# MCU.net
KiCad netlist of a schematic drawn in Altium Designer
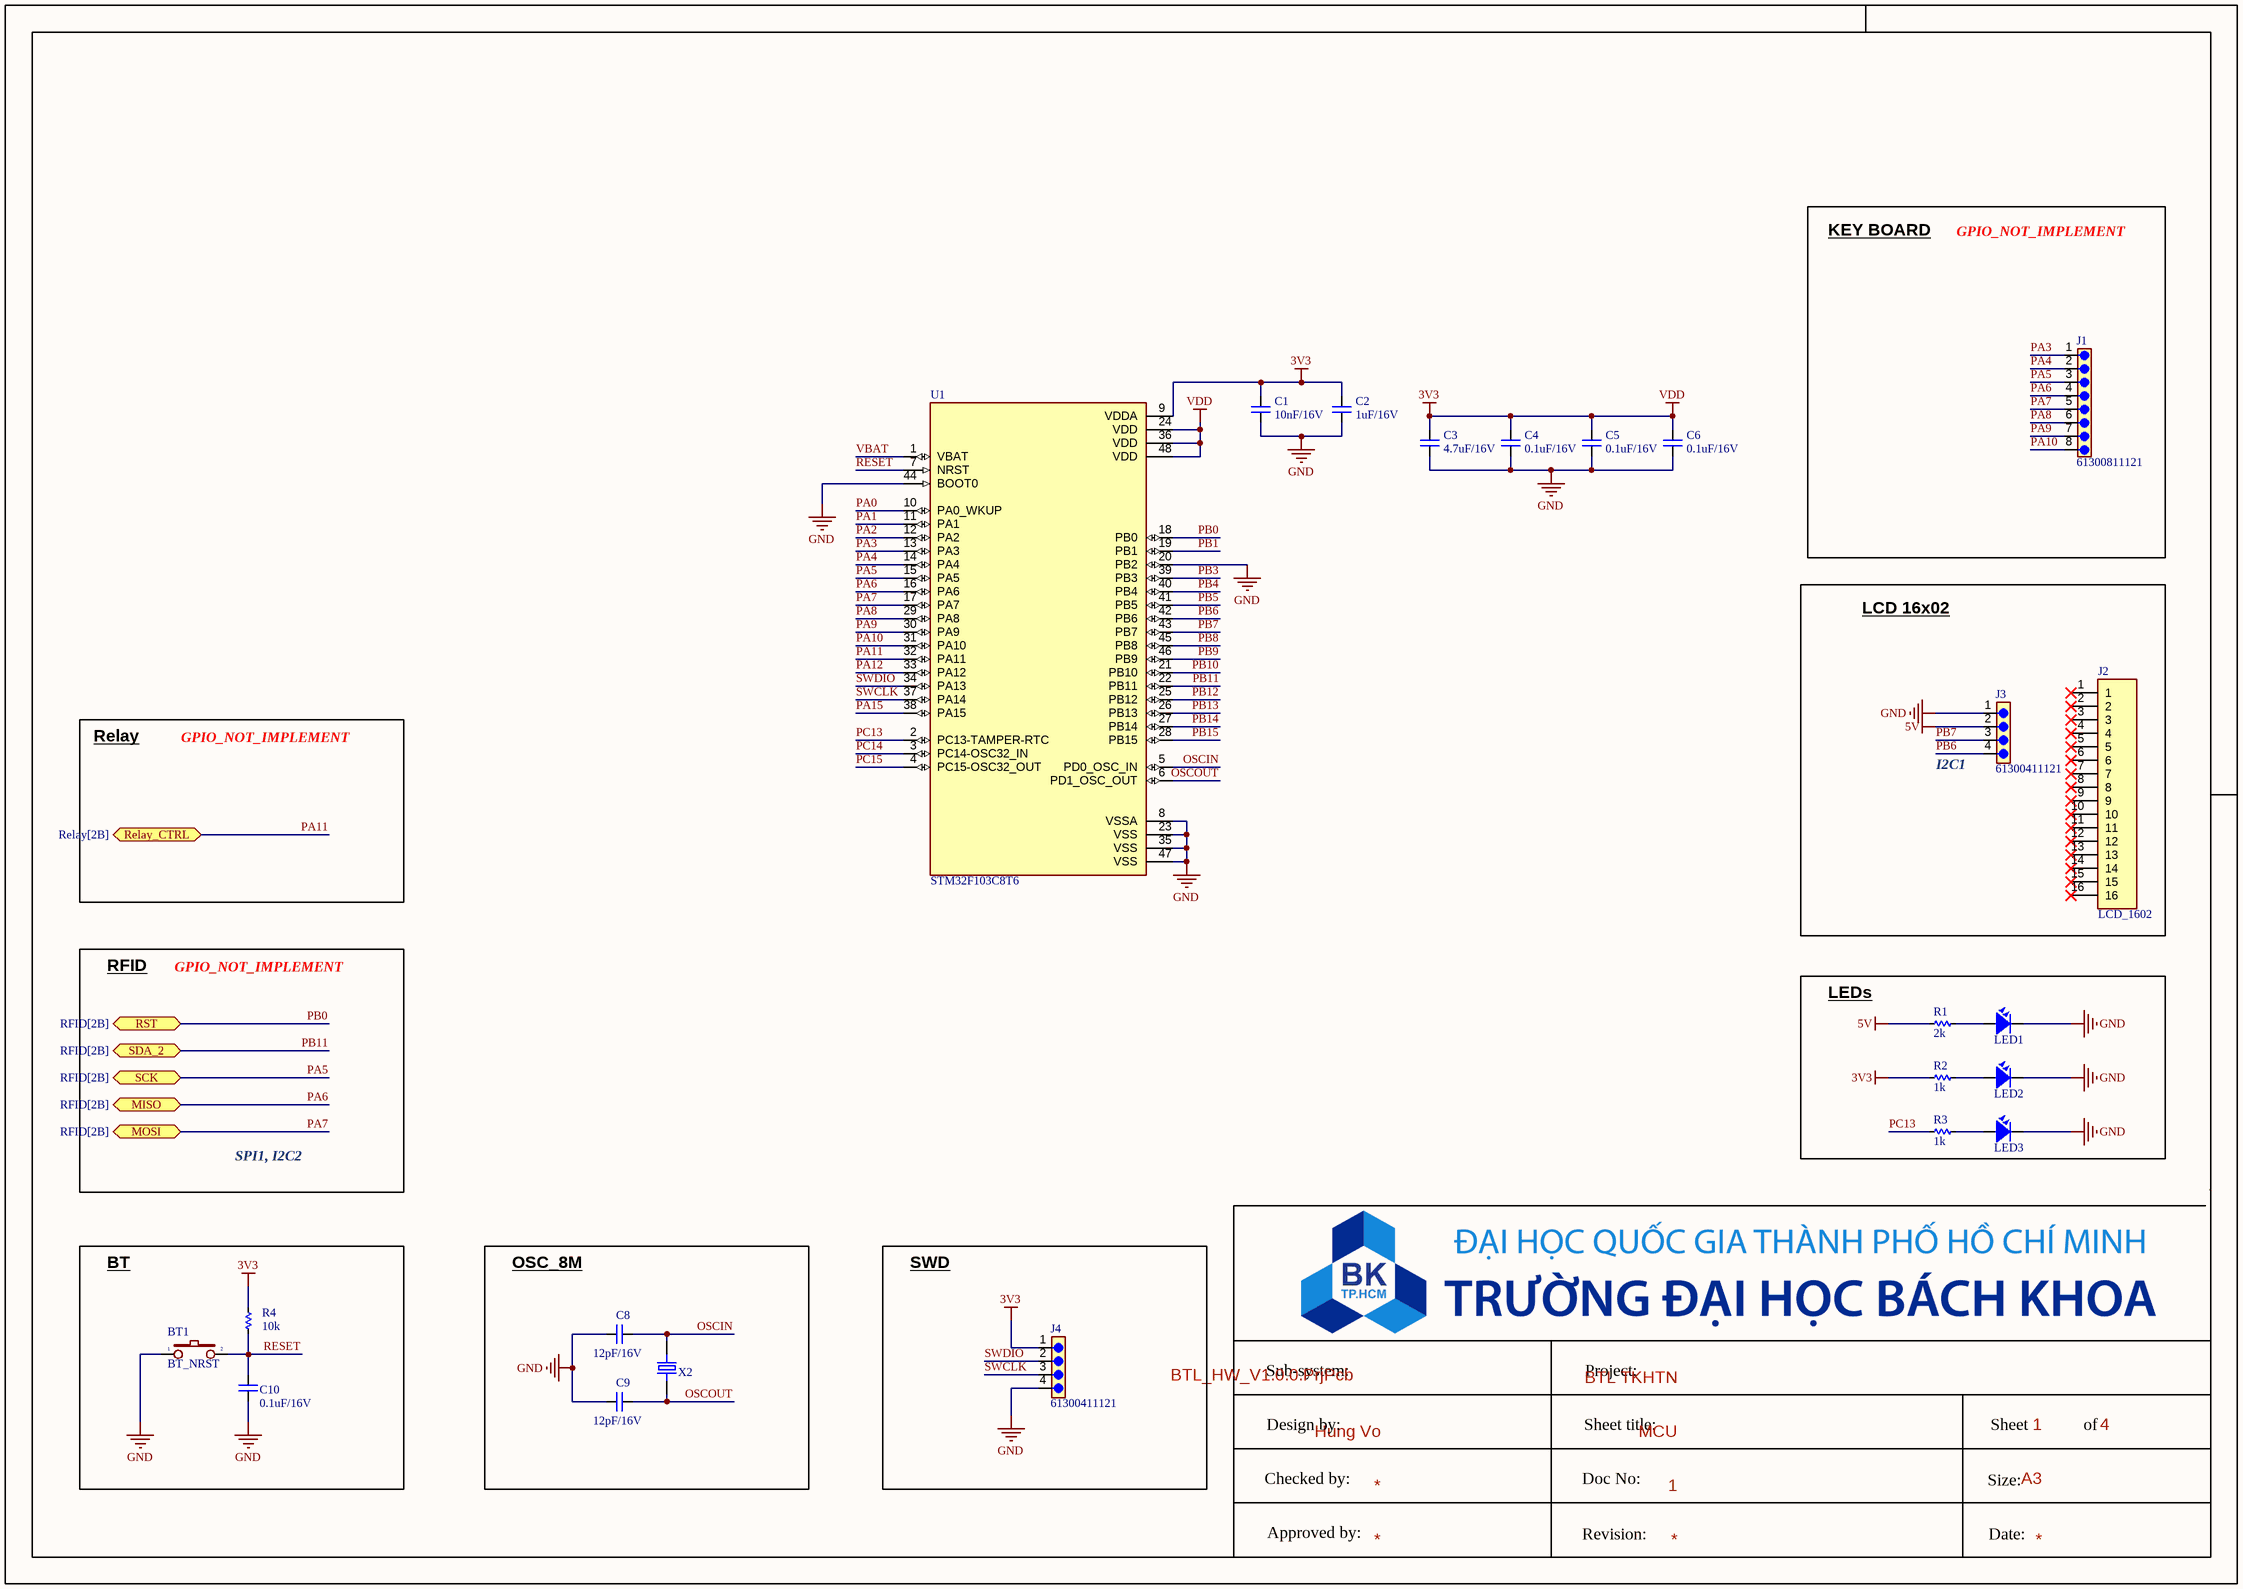
[diagram p0: MCU.SchDoc]

(export (version "E")
  (design (tool "Eeschema 10.0.6"))
  (components
    (comp (ref "BT1")
      (value "BT_NRST")
      (footprint "SW2-SMD")
      (description "Switch button 2 pin")
      (libsource (lib "C26_SCHLIB") (part "BT2"))
    )
    (comp (ref "C1")
      (value "10nF/16V")
      (footprint "CAP_C_1608X80")
      (description "CAP_Chip")
      (libsource (lib "C26_SCHLIB") (part "CAP_SMD"))
    )
    (comp (ref "C2")
      (value "1uF/16V")
      (footprint "CAP_C_1608X80")
      (description "CAP_Chip")
      (libsource (lib "C26_SCHLIB") (part "CAP_SMD"))
    )
    (comp (ref "C3")
      (value "4.7uF/16V")
      (footprint "CAP_C_1608X80")
      (description "CAP_Chip")
      (libsource (lib "C26_SCHLIB") (part "CAP_SMD"))
    )
    (comp (ref "C4")
      (value "0.1uF/16V")
      (footprint "CAP_C_1608X80")
      (description "CAP_Chip")
      (libsource (lib "C26_SCHLIB") (part "CAP_SMD"))
    )
    (comp (ref "C5")
      (value "0.1uF/16V")
      (footprint "CAP_C_1608X80")
      (description "CAP_Chip")
      (libsource (lib "C26_SCHLIB") (part "CAP_SMD"))
    )
    (comp (ref "C6")
      (value "0.1uF/16V")
      (footprint "CAP_C_1608X80")
      (description "CAP_Chip")
      (libsource (lib "C26_SCHLIB") (part "CAP_SMD"))
    )
    (comp (ref "C8")
      (value "12pF/16V")
      (footprint "CAP_C_1608X80")
      (description "CAP_Chip")
      (libsource (lib "C26_SCHLIB") (part "CAP_SMD"))
    )
    (comp (ref "C9")
      (value "12pF/16V")
      (footprint "CAP_C_1608X80")
      (description "CAP_Chip")
      (libsource (lib "C26_SCHLIB") (part "CAP_SMD"))
    )
    (comp (ref "C10")
      (value "0.1uF/16V")
      (footprint "CAP_C_1608X80")
      (description "CAP_Chip")
      (libsource (lib "C26_SCHLIB") (part "CAP_SMD"))
    )
    (comp (ref "J1")
      (value "61300811121")
      (footprint "61300811121")
      (description "8 pins, 1 row, straight, gold plating")
      (fields (field (name "MF") "Wurth Electronics"))
      (libsource (lib "BTL_SCHLIB") (part "61300811121"))
    )
    (comp (ref "J2")
      (value "LCD_1602")
      (footprint "LCD_1602")
      (libsource (lib "BTL_SCHLIB") (part "LCD_1602"))
    )
    (comp (ref "J3")
      (value "61300411121")
      (footprint "61300411121")
      (description "CONN HEADER VERT 4POS 2.54MM")
      (fields (field (name "MF") "WÃ¼rth Elektronik"))
      (libsource (lib "BTL_SCHLIB") (part "61300411121"))
    )
    (comp (ref "J4")
      (value "61300411121")
      (footprint "61300411121")
      (description "CONN HEADER VERT 4POS 2.54MM")
      (fields (field (name "MF") "WÃ¼rth Elektronik"))
      (libsource (lib "C26_SCHLIB") (part "61300411121"))
    )
    (comp (ref "LED1")
      (value "LED")
      (footprint "LED-0603-RED")
      (libsource (lib "C26_SCHLIB") (part "LED SMD"))
    )
    (comp (ref "LED2")
      (value "LED")
      (footprint "LED-0603-RED")
      (libsource (lib "C26_SCHLIB") (part "LED SMD"))
    )
    (comp (ref "LED3")
      (value "LED")
      (footprint "LED-0603-RED")
      (libsource (lib "C26_SCHLIB") (part "LED SMD"))
    )
    (comp (ref "R1")
      (value "2k")
      (footprint "RES_C_1608X60")
      (description "RES")
      (libsource (lib "C26_SCHLIB") (part "RES_SMD"))
    )
    (comp (ref "R2")
      (value "1k")
      (footprint "RES_C_1608X60")
      (description "RES")
      (libsource (lib "C26_SCHLIB") (part "RES_SMD"))
    )
    (comp (ref "R3")
      (value "1k")
      (footprint "RES_C_1608X60")
      (description "RES")
      (libsource (lib "C26_SCHLIB") (part "RES_SMD"))
    )
    (comp (ref "R4")
      (value "10k")
      (footprint "RES_C_1608X60")
      (description "RES")
      (libsource (lib "C26_SCHLIB") (part "RES_SMD"))
    )
    (comp (ref "U1")
      (value "STM32F103C8T6")
      (footprint "QFP50P900X900X160-48N")
      (description "ARM® Cortex®-M3 STM32F1 Microcontroller IC 32-Bit 72MHz 64KB (64K x 8) FLASH 48-LQFP (7x7)")
      (fields (field (name "MF") "STMicroelectronics"))
      (libsource (lib "C26_SCHLIB") (part "STM32F103C8T6"))
    )
    (comp (ref "X2")
      (value "ECS-080-18-5PX-JES-TR")
      (footprint "XTAL 8MHz")
      (description "8 MHz Â±20ppm Crystal 18pF 60 Ohms HC-49/US")
      (fields (field (name "MF") "ECS Inc."))
      (libsource (lib "C26_SCHLIB") (part "ECS-080-18-5PX-JES-TR"))
    )
  )
  (nets
    (net (code "1") (name "/OSCIN") (class "Default")
      (node (ref "C8") (pin "2") (pinfunction "2_2") (pintype "passive"))
      (node (ref "U1") (pin "5") (pinfunction "PD0_OSC_IN_5") (pintype "bidirectional"))
      (node (ref "X2") (pin "1") (pinfunction "1_1") (pintype "passive"))
    )
    (net (code "2") (name "/OSCOUT") (class "Default")
      (node (ref "C9") (pin "2") (pinfunction "2_2") (pintype "passive"))
      (node (ref "U1") (pin "6") (pinfunction "PD1_OSC_OUT_6") (pintype "bidirectional"))
      (node (ref "X2") (pin "2") (pinfunction "2_2") (pintype "passive"))
    )
    (net (code "3") (name "/PA0") (class "Default")
      (node (ref "U1") (pin "10") (pinfunction "PA0_WKUP_10") (pintype "bidirectional"))
    )
    (net (code "4") (name "/PA1") (class "Default")
      (node (ref "U1") (pin "11") (pinfunction "PA1_11") (pintype "bidirectional"))
    )
    (net (code "5") (name "/PA2") (class "Default")
      (node (ref "U1") (pin "12") (pinfunction "PA2_12") (pintype "bidirectional"))
    )
    (net (code "6") (name "/PA3") (class "Default")
      (node (ref "J1") (pin "1") (pinfunction "1_1") (pintype "passive"))
      (node (ref "U1") (pin "13") (pinfunction "PA3_13") (pintype "bidirectional"))
    )
    (net (code "7") (name "/PA4") (class "Default")
      (node (ref "J1") (pin "2") (pinfunction "2_2") (pintype "passive"))
      (node (ref "U1") (pin "14") (pinfunction "PA4_14") (pintype "bidirectional"))
    )
    (net (code "8") (name "/PA5") (class "Default")
      (node (ref "J1") (pin "3") (pinfunction "3_3") (pintype "passive"))
      (node (ref "U1") (pin "15") (pinfunction "PA5_15") (pintype "bidirectional"))
    )
    (net (code "9") (name "/PA6") (class "Default")
      (node (ref "J1") (pin "4") (pinfunction "4_4") (pintype "passive"))
      (node (ref "U1") (pin "16") (pinfunction "PA6_16") (pintype "bidirectional"))
    )
    (net (code "10") (name "/PA7") (class "Default")
      (node (ref "J1") (pin "5") (pinfunction "5_5") (pintype "passive"))
      (node (ref "U1") (pin "17") (pinfunction "PA7_17") (pintype "bidirectional"))
    )
    (net (code "11") (name "/PA8") (class "Default")
      (node (ref "J1") (pin "6") (pinfunction "6_6") (pintype "passive"))
      (node (ref "U1") (pin "29") (pinfunction "PA8_29") (pintype "bidirectional"))
    )
    (net (code "12") (name "/PA9") (class "Default")
      (node (ref "J1") (pin "7") (pinfunction "7_7") (pintype "passive"))
      (node (ref "U1") (pin "30") (pinfunction "PA9_30") (pintype "bidirectional"))
    )
    (net (code "13") (name "/PA10") (class "Default")
      (node (ref "J1") (pin "8") (pinfunction "8_8") (pintype "passive"))
      (node (ref "U1") (pin "31") (pinfunction "PA10_31") (pintype "bidirectional"))
    )
    (net (code "14") (name "/PA11") (class "Default")
      (node (ref "U1") (pin "32") (pinfunction "PA11_32") (pintype "bidirectional"))
    )
    (net (code "15") (name "/PA12") (class "Default")
      (node (ref "U1") (pin "33") (pinfunction "PA12_33") (pintype "bidirectional"))
    )
    (net (code "16") (name "/PA15") (class "Default")
      (node (ref "U1") (pin "38") (pinfunction "PA15_38") (pintype "bidirectional"))
    )
    (net (code "17") (name "/PB0") (class "Default")
      (node (ref "U1") (pin "18") (pinfunction "PB0_18") (pintype "bidirectional"))
    )
    (net (code "18") (name "/PB1") (class "Default")
      (node (ref "U1") (pin "19") (pinfunction "PB1_19") (pintype "bidirectional"))
    )
    (net (code "19") (name "/PB3") (class "Default")
      (node (ref "U1") (pin "39") (pinfunction "PB3_39") (pintype "bidirectional"))
    )
    (net (code "20") (name "/PB4") (class "Default")
      (node (ref "U1") (pin "40") (pinfunction "PB4_40") (pintype "bidirectional"))
    )
    (net (code "21") (name "/PB5") (class "Default")
      (node (ref "U1") (pin "41") (pinfunction "PB5_41") (pintype "bidirectional"))
    )
    (net (code "22") (name "/PB6") (class "Default")
      (node (ref "J3") (pin "4") (pinfunction "4_4") (pintype "passive"))
      (node (ref "U1") (pin "42") (pinfunction "PB6_42") (pintype "bidirectional"))
    )
    (net (code "23") (name "/PB7") (class "Default")
      (node (ref "J3") (pin "3") (pinfunction "3_3") (pintype "passive"))
      (node (ref "U1") (pin "43") (pinfunction "PB7_43") (pintype "bidirectional"))
    )
    (net (code "24") (name "/PB8") (class "Default")
      (node (ref "U1") (pin "45") (pinfunction "PB8_45") (pintype "bidirectional"))
    )
    (net (code "25") (name "/PB9") (class "Default")
      (node (ref "U1") (pin "46") (pinfunction "PB9_46") (pintype "bidirectional"))
    )
    (net (code "26") (name "/PB10") (class "Default")
      (node (ref "U1") (pin "21") (pinfunction "PB10_21") (pintype "bidirectional"))
    )
    (net (code "27") (name "/PB11") (class "Default")
      (node (ref "U1") (pin "22") (pinfunction "PB11_22") (pintype "bidirectional"))
    )
    (net (code "28") (name "/PB12") (class "Default")
      (node (ref "U1") (pin "25") (pinfunction "PB12_25") (pintype "bidirectional"))
    )
    (net (code "29") (name "/PB13") (class "Default")
      (node (ref "U1") (pin "26") (pinfunction "PB13_26") (pintype "bidirectional"))
    )
    (net (code "30") (name "/PB14") (class "Default")
      (node (ref "U1") (pin "27") (pinfunction "PB14_27") (pintype "bidirectional"))
    )
    (net (code "31") (name "/PB15") (class "Default")
      (node (ref "U1") (pin "28") (pinfunction "PB15_28") (pintype "bidirectional"))
    )
    (net (code "32") (name "/PC13") (class "Default")
      (node (ref "R3") (pin "2") (pinfunction "2_2") (pintype "passive"))
      (node (ref "U1") (pin "2") (pinfunction "PC13-TAMPER-RTC_2") (pintype "bidirectional"))
    )
    (net (code "33") (name "/PC14") (class "Default")
      (node (ref "U1") (pin "3") (pinfunction "PC14-OSC32_IN_3") (pintype "bidirectional"))
    )
    (net (code "34") (name "/PC15") (class "Default")
      (node (ref "U1") (pin "4") (pinfunction "PC15-OSC32_OUT_4") (pintype "bidirectional"))
    )
    (net (code "35") (name "/RESET") (class "Default")
      (node (ref "BT1") (pin "2") (pinfunction "2_2") (pintype "passive"))
      (node (ref "C10") (pin "2") (pinfunction "2_2") (pintype "passive"))
      (node (ref "R4") (pin "1") (pinfunction "1_1") (pintype "passive"))
      (node (ref "U1") (pin "7") (pinfunction "NRST_7") (pintype "input"))
    )
    (net (code "36") (name "/SWCLK") (class "Default")
      (node (ref "J4") (pin "3") (pinfunction "3_3") (pintype "passive"))
      (node (ref "U1") (pin "37") (pinfunction "PA14_37") (pintype "bidirectional"))
    )
    (net (code "37") (name "/SWDIO") (class "Default")
      (node (ref "J4") (pin "2") (pinfunction "2_2") (pintype "passive"))
      (node (ref "U1") (pin "34") (pinfunction "PA13_34") (pintype "bidirectional"))
    )
    (net (code "38") (name "/VBAT") (class "Default")
      (node (ref "U1") (pin "1") (pinfunction "VBAT_1") (pintype "bidirectional"))
    )
    (net (code "39") (name "3V3") (class "Default")
      (node (ref "C1") (pin "2") (pinfunction "2_2") (pintype "passive"))
      (node (ref "C2") (pin "2") (pinfunction "2_2") (pintype "passive"))
      (node (ref "C3") (pin "2") (pinfunction "2_2") (pintype "passive"))
      (node (ref "C4") (pin "2") (pinfunction "2_2") (pintype "passive"))
      (node (ref "C5") (pin "2") (pinfunction "2_2") (pintype "passive"))
      (node (ref "C6") (pin "2") (pinfunction "2_2") (pintype "passive"))
      (node (ref "J4") (pin "1") (pinfunction "1_1") (pintype "passive"))
      (node (ref "R2") (pin "2") (pinfunction "2_2") (pintype "passive"))
      (node (ref "R4") (pin "2") (pinfunction "2_2") (pintype "passive"))
      (node (ref "U1") (pin "24") (pinfunction "VDD_24") (pintype "power_in"))
      (node (ref "U1") (pin "36") (pinfunction "VDD_36") (pintype "power_in"))
      (node (ref "U1") (pin "48") (pinfunction "VDD_48") (pintype "power_in"))
      (node (ref "U1") (pin "9") (pinfunction "VDDA_9") (pintype "power_in"))
    )
    (net (code "40") (name "5V") (class "Default")
      (node (ref "J3") (pin "2") (pinfunction "2_2") (pintype "passive"))
      (node (ref "R1") (pin "2") (pinfunction "2_2") (pintype "passive"))
    )
    (net (code "41") (name "GND") (class "Default")
      (node (ref "BT1") (pin "1") (pinfunction "1_1") (pintype "passive"))
      (node (ref "C1") (pin "1") (pinfunction "1_1") (pintype "passive"))
      (node (ref "C10") (pin "1") (pinfunction "1_1") (pintype "passive"))
      (node (ref "C2") (pin "1") (pinfunction "1_1") (pintype "passive"))
      (node (ref "C3") (pin "1") (pinfunction "1_1") (pintype "passive"))
      (node (ref "C4") (pin "1") (pinfunction "1_1") (pintype "passive"))
      (node (ref "C5") (pin "1") (pinfunction "1_1") (pintype "passive"))
      (node (ref "C6") (pin "1") (pinfunction "1_1") (pintype "passive"))
      (node (ref "C8") (pin "1") (pinfunction "1_1") (pintype "passive"))
      (node (ref "C9") (pin "1") (pinfunction "1_1") (pintype "passive"))
      (node (ref "J3") (pin "1") (pinfunction "1_1") (pintype "passive"))
      (node (ref "J4") (pin "4") (pinfunction "4_4") (pintype "passive"))
      (node (ref "LED1") (pin "2") (pinfunction "2_2") (pintype "passive"))
      (node (ref "LED2") (pin "2") (pinfunction "2_2") (pintype "passive"))
      (node (ref "LED3") (pin "2") (pinfunction "2_2") (pintype "passive"))
      (node (ref "U1") (pin "20") (pinfunction "PB2_20") (pintype "bidirectional"))
      (node (ref "U1") (pin "23") (pinfunction "VSS_23") (pintype "power_in"))
      (node (ref "U1") (pin "35") (pinfunction "VSS_35") (pintype "power_in"))
      (node (ref "U1") (pin "44") (pinfunction "BOOT0_44") (pintype "input"))
      (node (ref "U1") (pin "47") (pinfunction "VSS_47") (pintype "power_in"))
      (node (ref "U1") (pin "8") (pinfunction "VSSA_8") (pintype "power_in"))
    )
    (net (code "42") (name "Net-(LED1-Pad1)") (class "Default")
      (node (ref "LED1") (pin "1") (pinfunction "1_1") (pintype "passive"))
      (node (ref "R1") (pin "1") (pinfunction "1_1") (pintype "passive"))
    )
    (net (code "43") (name "Net-(LED2-Pad1)") (class "Default")
      (node (ref "LED2") (pin "1") (pinfunction "1_1") (pintype "passive"))
      (node (ref "R2") (pin "1") (pinfunction "1_1") (pintype "passive"))
    )
    (net (code "44") (name "Net-(LED3-Pad1)") (class "Default")
      (node (ref "LED3") (pin "1") (pinfunction "1_1") (pintype "passive"))
      (node (ref "R3") (pin "1") (pinfunction "1_1") (pintype "passive"))
    )
    (net (code "45") (name "unconnected-(J2-Pad1)") (class "Default")
      (node (ref "J2") (pin "1") (pinfunction "1_1") (pintype "passive+no_connect"))
    )
    (net (code "46") (name "unconnected-(J2-Pad2)") (class "Default")
      (node (ref "J2") (pin "2") (pinfunction "2_2") (pintype "passive+no_connect"))
    )
    (net (code "47") (name "unconnected-(J2-Pad3)") (class "Default")
      (node (ref "J2") (pin "3") (pinfunction "3_3") (pintype "passive+no_connect"))
    )
    (net (code "48") (name "unconnected-(J2-Pad4)") (class "Default")
      (node (ref "J2") (pin "4") (pinfunction "4_4") (pintype "passive+no_connect"))
    )
    (net (code "49") (name "unconnected-(J2-Pad5)") (class "Default")
      (node (ref "J2") (pin "5") (pinfunction "5_5") (pintype "passive+no_connect"))
    )
    (net (code "50") (name "unconnected-(J2-Pad6)") (class "Default")
      (node (ref "J2") (pin "6") (pinfunction "6_6") (pintype "passive+no_connect"))
    )
    (net (code "51") (name "unconnected-(J2-Pad7)") (class "Default")
      (node (ref "J2") (pin "7") (pinfunction "7_7") (pintype "passive+no_connect"))
    )
    (net (code "52") (name "unconnected-(J2-Pad8)") (class "Default")
      (node (ref "J2") (pin "8") (pinfunction "8_8") (pintype "passive+no_connect"))
    )
    (net (code "53") (name "unconnected-(J2-Pad9)") (class "Default")
      (node (ref "J2") (pin "9") (pinfunction "9_9") (pintype "passive+no_connect"))
    )
    (net (code "54") (name "unconnected-(J2-Pad10)") (class "Default")
      (node (ref "J2") (pin "10") (pinfunction "10_10") (pintype "passive+no_connect"))
    )
    (net (code "55") (name "unconnected-(J2-Pad11)") (class "Default")
      (node (ref "J2") (pin "11") (pinfunction "11_11") (pintype "passive+no_connect"))
    )
    (net (code "56") (name "unconnected-(J2-Pad12)") (class "Default")
      (node (ref "J2") (pin "12") (pinfunction "12_12") (pintype "passive+no_connect"))
    )
    (net (code "57") (name "unconnected-(J2-Pad13)") (class "Default")
      (node (ref "J2") (pin "13") (pinfunction "13_13") (pintype "passive+no_connect"))
    )
    (net (code "58") (name "unconnected-(J2-Pad14)") (class "Default")
      (node (ref "J2") (pin "14") (pinfunction "14_14") (pintype "passive+no_connect"))
    )
    (net (code "59") (name "unconnected-(J2-Pad15)") (class "Default")
      (node (ref "J2") (pin "15") (pinfunction "15_15") (pintype "passive+no_connect"))
    )
    (net (code "60") (name "unconnected-(J2-Pad16)") (class "Default")
      (node (ref "J2") (pin "16") (pinfunction "16_16") (pintype "passive+no_connect"))
    )
  )
)
